# Sheet1.net
KiCad netlist of a schematic drawn in Altium Designer
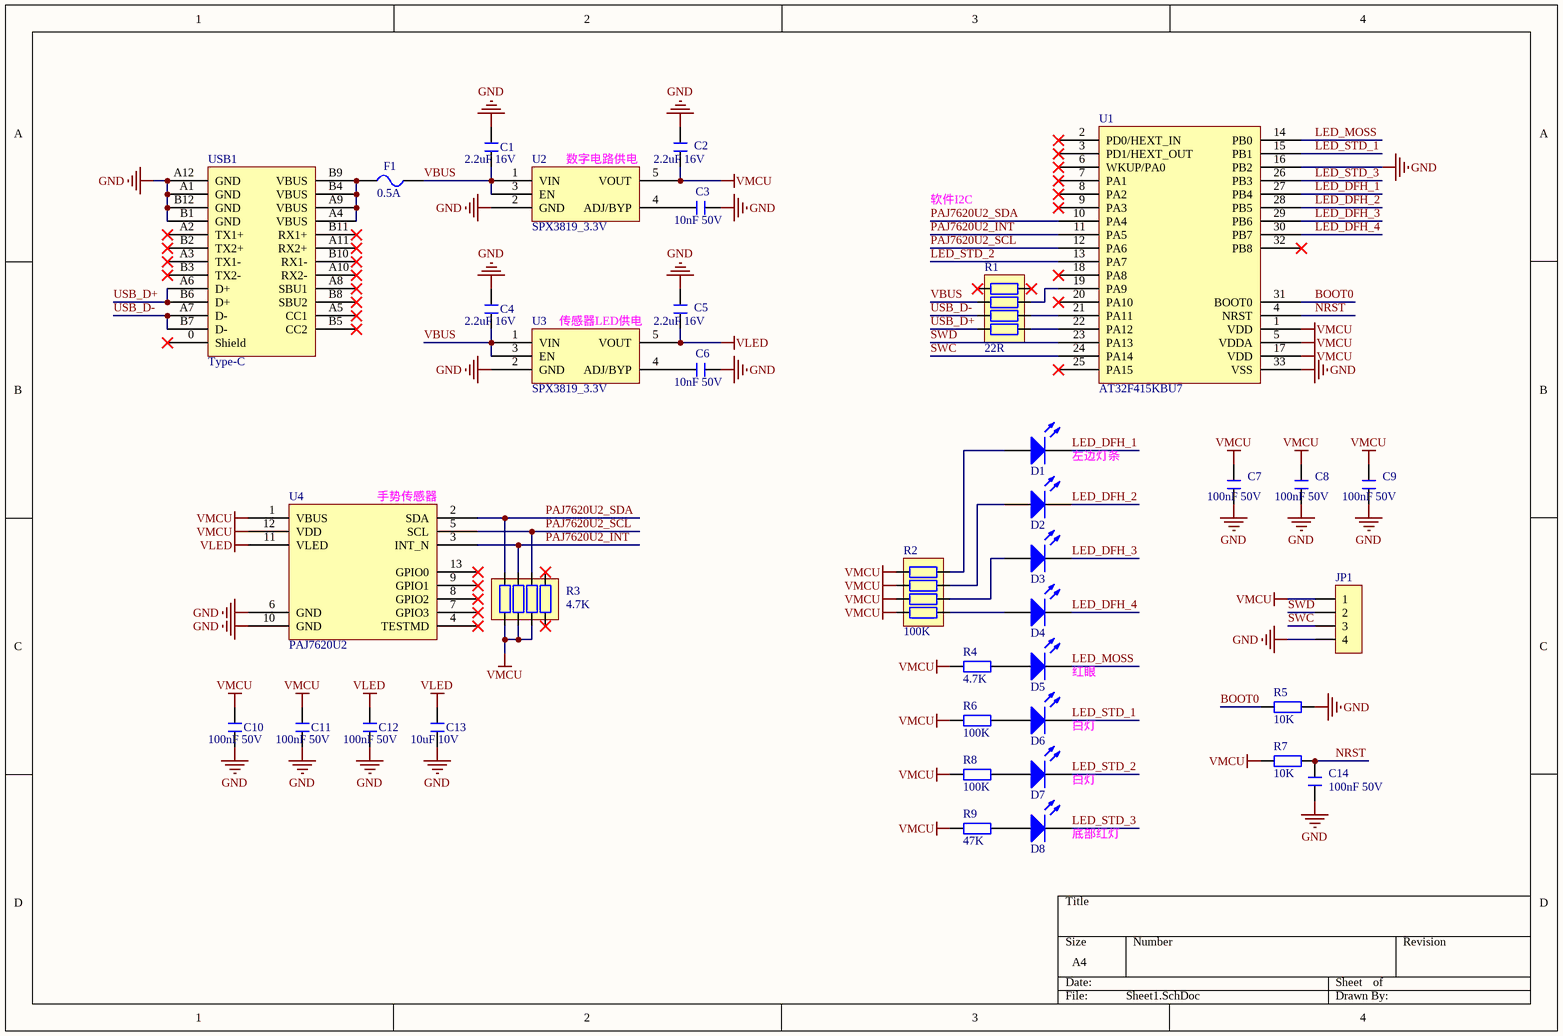
[diagram p0: Sheet1.SchDoc]

(export (version "E")
  (design (tool "Eeschema 10.0.6"))
  (components
    (comp (ref "C1")
      (value "2.2uF 16V")
      (footprint "C 0603_L")
      (description "贴片电容")
      (libsource (lib "0.1 - 电阻-电容-电感") (part "C"))
    )
    (comp (ref "C2")
      (value "2.2uF 16V")
      (footprint "C 0603_L")
      (description "贴片电容")
      (libsource (lib "0.1 - 电阻-电容-电感") (part "C"))
    )
    (comp (ref "C3")
      (value "10nF 50V")
      (footprint "C 0603_L")
      (description "贴片电容")
      (libsource (lib "0.1 - 电阻-电容-电感") (part "C"))
    )
    (comp (ref "C4")
      (value "2.2uF 16V")
      (footprint "C 0603_L")
      (description "贴片电容")
      (libsource (lib "0.1 - 电阻-电容-电感") (part "C"))
    )
    (comp (ref "C5")
      (value "2.2uF 16V")
      (footprint "C 0603_L")
      (description "贴片电容")
      (libsource (lib "0.1 - 电阻-电容-电感") (part "C"))
    )
    (comp (ref "C6")
      (value "10nF 50V")
      (footprint "C 0603_L")
      (description "贴片电容")
      (libsource (lib "0.1 - 电阻-电容-电感") (part "C"))
    )
    (comp (ref "C7")
      (value "100nF 50V")
      (footprint "C 0603_L")
      (description "贴片电容")
      (libsource (lib "0.1 - 电阻-电容-电感") (part "C"))
    )
    (comp (ref "C8")
      (value "100nF 50V")
      (footprint "C 0603_L")
      (description "贴片电容")
      (libsource (lib "0.1 - 电阻-电容-电感") (part "C"))
    )
    (comp (ref "C9")
      (value "100nF 50V")
      (footprint "C 0603_L")
      (description "贴片电容")
      (libsource (lib "0.1 - 电阻-电容-电感") (part "C"))
    )
    (comp (ref "C10")
      (value "100nF 50V")
      (footprint "C 0603_L")
      (description "贴片电容")
      (libsource (lib "0.1 - 电阻-电容-电感") (part "C"))
    )
    (comp (ref "C11")
      (value "100nF 50V")
      (footprint "C 0603_L")
      (description "贴片电容")
      (libsource (lib "0.1 - 电阻-电容-电感") (part "C"))
    )
    (comp (ref "C12")
      (value "100nF 50V")
      (footprint "C 0603_L")
      (description "贴片电容")
      (libsource (lib "0.1 - 电阻-电容-电感") (part "C"))
    )
    (comp (ref "C13")
      (value "10uF 10V")
      (footprint "C 0603_L")
      (description "贴片电容")
      (libsource (lib "0.1 - 电阻-电容-电感") (part "C"))
    )
    (comp (ref "C14")
      (value "100nF 50V")
      (footprint "C 0603_L")
      (description "贴片电容")
      (libsource (lib "0.1 - 电阻-电容-电感") (part "C"))
    )
    (comp (ref "D1")
      (value "LED")
      (footprint "R 0402_L")
      (description "发光二极管")
      (libsource (lib "0.3 - LED发光二极管") (part "LED"))
    )
    (comp (ref "D2")
      (value "LED")
      (footprint "R 0402_L")
      (description "发光二极管")
      (libsource (lib "0.3 - LED发光二极管") (part "LED"))
    )
    (comp (ref "D3")
      (value "LED")
      (footprint "R 0402_L")
      (description "发光二极管")
      (libsource (lib "0.3 - LED发光二极管") (part "LED"))
    )
    (comp (ref "D4")
      (value "LED")
      (footprint "R 0402_L")
      (description "发光二极管")
      (libsource (lib "0.3 - LED发光二极管") (part "LED"))
    )
    (comp (ref "D5")
      (value "LED")
      (footprint "LED_0603")
      (description "发光二极管")
      (libsource (lib "0.3 - LED发光二极管") (part "LED"))
    )
    (comp (ref "D6")
      (value "LED")
      (footprint "R 0402_L")
      (description "发光二极管")
      (libsource (lib "0.3 - LED发光二极管") (part "LED"))
    )
    (comp (ref "D7")
      (value "LED")
      (footprint "R 0402_L")
      (description "发光二极管")
      (libsource (lib "0.3 - LED发光二极管") (part "LED"))
    )
    (comp (ref "D8")
      (value "LED")
      (footprint "LED_0603")
      (description "发光二极管")
      (libsource (lib "0.3 - LED发光二极管") (part "LED"))
    )
    (comp (ref "F1")
      (value "0.5A")
      (footprint "FU 0805")
      (description "贴片保险丝")
      (fields (field (name "版权归属") "封装库来自淘宝卖家 ID：黄晶宝石"))
      (libsource (lib "0.5 - 保险丝-晶振-光耦") (part "FU"))
    )
    (comp (ref "JP1")
      (value "HDR-1X4")
      (footprint "HDR2.54-LI-4P")
      (description "4P接插件")
      (libsource (lib "5.1 - 接插件-脚距1.27") (part "Header 4"))
    )
    (comp (ref "R1")
      (value "22R")
      (footprint "RCA-8P4R-0603")
      (description "贴片排阻")
      (libsource (lib "0.1 - 电阻-电容-电感") (part "R-8P4R"))
    )
    (comp (ref "R2")
      (value "100K")
      (footprint "RCA-8P4R-0603")
      (description "贴片排阻")
      (libsource (lib "0.1 - 电阻-电容-电感") (part "R-8P4R"))
    )
    (comp (ref "R3")
      (value "4.7K")
      (footprint "RCA-8P4R-0603")
      (description "贴片排阻")
      (libsource (lib "") (part "R-8P4R_1"))
    )
    (comp (ref "R4")
      (value "4.7K")
      (footprint "R 0603_L")
      (description "贴片电阻")
      (libsource (lib "0.1 - 电阻-电容-电感") (part "R"))
    )
    (comp (ref "R5")
      (value "10K")
      (footprint "R 0603_L")
      (description "贴片电阻")
      (libsource (lib "0.1 - 电阻-电容-电感") (part "R"))
    )
    (comp (ref "R6")
      (value "100K")
      (footprint "R 0603_L")
      (description "贴片电阻")
      (libsource (lib "0.1 - 电阻-电容-电感") (part "R"))
    )
    (comp (ref "R7")
      (value "10K")
      (footprint "R 0603_L")
      (description "贴片电阻")
      (libsource (lib "0.1 - 电阻-电容-电感") (part "R"))
    )
    (comp (ref "R8")
      (value "100K")
      (footprint "R 0603_L")
      (description "贴片电阻")
      (libsource (lib "0.1 - 电阻-电容-电感") (part "R"))
    )
    (comp (ref "R9")
      (value "47K")
      (footprint "R 0603_L")
      (description "贴片电阻")
      (libsource (lib "0.1 - 电阻-电容-电感") (part "R"))
    )
    (comp (ref "U1")
      (value "AT32F415KBU7")
      (footprint "QFN-32 4X4")
      (description "基于ARM® 32位的Cortex®\r\n-M4微控制器，带64 K字节至256 K字节闪存、sLib、OTGFS、11个定时器、1个ADC、2个比较器、12个通信接口")
      (libsource (lib "mysch") (part "AT32F415K"))
    )
    (comp (ref "U2")
      (value "SPX3819_3.3V")
      (footprint "SOT23-5n")
      (description "16V 500mA LDO")
      (libsource (lib "mysch") (part "SPX3819"))
    )
    (comp (ref "U3")
      (value "SPX3819_3.3V")
      (footprint "SOT23-5n")
      (description "16V 500mA LDO")
      (libsource (lib "mysch") (part "SPX3819"))
    )
    (comp (ref "U4")
      (value "PAJ7620U2")
      (footprint "QFN-13_L5.2-W3.0_PAJ7620U2")
      (description "手势识别传感器")
      (libsource (lib "mysch") (part "PAJ7620U2"))
    )
    (comp (ref "USB1")
      (value "Type-C")
      (footprint "USB-TYPE-C_16PIN-MALE-TYPE-C-31-M-12")
      (libsource (lib "type-c") (part "Type-C"))
    )
  )
  (nets
    (net (code "1") (name "/BOOT0") (class "Default")
      (node (ref "R5") (pin "2") (pinfunction "2_2") (pintype "passive"))
      (node (ref "U1") (pin "31") (pinfunction "BOOT0_31") (pintype "passive"))
    )
    (net (code "2") (name "/LED_DFH_1") (class "Default")
      (node (ref "D1") (pin "2") (pinfunction "K_2") (pintype "passive"))
      (node (ref "U1") (pin "27") (pinfunction "PB4_27") (pintype "passive"))
    )
    (net (code "3") (name "/LED_DFH_2") (class "Default")
      (node (ref "D2") (pin "2") (pinfunction "K_2") (pintype "passive"))
      (node (ref "U1") (pin "28") (pinfunction "PB5_28") (pintype "passive"))
    )
    (net (code "4") (name "/LED_DFH_3") (class "Default")
      (node (ref "D3") (pin "2") (pinfunction "K_2") (pintype "passive"))
      (node (ref "U1") (pin "29") (pinfunction "PB6_29") (pintype "passive"))
    )
    (net (code "5") (name "/LED_DFH_4") (class "Default")
      (node (ref "D4") (pin "2") (pinfunction "K_2") (pintype "passive"))
      (node (ref "U1") (pin "30") (pinfunction "PB7_30") (pintype "passive"))
    )
    (net (code "6") (name "/LED_MOSS") (class "Default")
      (node (ref "D5") (pin "2") (pinfunction "K_2") (pintype "passive"))
      (node (ref "U1") (pin "14") (pinfunction "PB0_14") (pintype "passive"))
    )
    (net (code "7") (name "/LED_STD_1") (class "Default")
      (node (ref "D6") (pin "2") (pinfunction "K_2") (pintype "passive"))
      (node (ref "U1") (pin "15") (pinfunction "PB1_15") (pintype "passive"))
    )
    (net (code "8") (name "/LED_STD_2") (class "Default")
      (node (ref "D7") (pin "2") (pinfunction "K_2") (pintype "passive"))
      (node (ref "U1") (pin "13") (pinfunction "PA7_13") (pintype "passive"))
    )
    (net (code "9") (name "/LED_STD_3") (class "Default")
      (node (ref "D8") (pin "2") (pinfunction "K_2") (pintype "passive"))
      (node (ref "U1") (pin "26") (pinfunction "PB3_26") (pintype "passive"))
    )
    (net (code "10") (name "/NRST") (class "Default")
      (node (ref "C14") (pin "2") (pinfunction "2_2") (pintype "passive"))
      (node (ref "R7") (pin "1") (pinfunction "1_1") (pintype "passive"))
      (node (ref "U1") (pin "4") (pinfunction "NRST_4") (pintype "passive"))
    )
    (net (code "11") (name "/PAJ7620U2_INT") (class "Default")
      (node (ref "R3") (pin "7") (pinfunction "7_7") (pintype "passive"))
      (node (ref "U1") (pin "11") (pinfunction "PA5_11") (pintype "passive"))
      (node (ref "U4") (pin "3") (pinfunction "INT_N_3") (pintype "passive"))
    )
    (net (code "12") (name "/PAJ7620U2_SCL") (class "Default")
      (node (ref "R3") (pin "6") (pinfunction "6_6") (pintype "passive"))
      (node (ref "U1") (pin "12") (pinfunction "PA6_12") (pintype "passive"))
      (node (ref "U4") (pin "5") (pinfunction "SCL_5") (pintype "passive"))
    )
    (net (code "13") (name "/PAJ7620U2_SDA") (class "Default")
      (node (ref "R3") (pin "8") (pinfunction "8_8") (pintype "passive"))
      (node (ref "U1") (pin "10") (pinfunction "PA4_10") (pintype "passive"))
      (node (ref "U4") (pin "2") (pinfunction "SDA_2") (pintype "passive"))
    )
    (net (code "14") (name "/SWC") (class "Default")
      (node (ref "JP1") (pin "3") (pinfunction "3_3") (pintype "passive"))
      (node (ref "U1") (pin "24") (pinfunction "PA14_24") (pintype "passive"))
    )
    (net (code "15") (name "/SWD") (class "Default")
      (node (ref "JP1") (pin "2") (pinfunction "2_2") (pintype "passive"))
      (node (ref "U1") (pin "23") (pinfunction "PA13_23") (pintype "passive"))
    )
    (net (code "16") (name "/USB_D+") (class "Default")
      (node (ref "R1") (pin "4") (pinfunction "4_4") (pintype "passive"))
      (node (ref "USB1") (pin "A6") (pinfunction "D+_A6") (pintype "passive"))
      (node (ref "USB1") (pin "B6") (pinfunction "D+_B6") (pintype "passive"))
    )
    (net (code "17") (name "/USB_D-") (class "Default")
      (node (ref "R1") (pin "3") (pinfunction "3_3") (pintype "passive"))
      (node (ref "USB1") (pin "A7") (pinfunction "D-_A7") (pintype "passive"))
      (node (ref "USB1") (pin "B7") (pinfunction "D-_B7") (pintype "passive"))
    )
    (net (code "18") (name "/VBUS") (class "Default")
      (node (ref "C1") (pin "1") (pinfunction "1_1") (pintype "passive"))
      (node (ref "C4") (pin "1") (pinfunction "1_1") (pintype "passive"))
      (node (ref "F1") (pin "2") (pinfunction "2_2") (pintype "passive"))
      (node (ref "R1") (pin "2") (pinfunction "2_2") (pintype "passive"))
      (node (ref "U2") (pin "1") (pinfunction "VIN_1") (pintype "passive"))
      (node (ref "U2") (pin "3") (pinfunction "EN_3") (pintype "passive"))
      (node (ref "U3") (pin "1") (pinfunction "VIN_1") (pintype "passive"))
      (node (ref "U3") (pin "3") (pinfunction "EN_3") (pintype "passive"))
    )
    (net (code "19") (name "GND") (class "Default")
      (node (ref "C1") (pin "2") (pinfunction "2_2") (pintype "passive"))
      (node (ref "C10") (pin "2") (pinfunction "2_2") (pintype "passive"))
      (node (ref "C11") (pin "2") (pinfunction "2_2") (pintype "passive"))
      (node (ref "C12") (pin "2") (pinfunction "2_2") (pintype "passive"))
      (node (ref "C13") (pin "2") (pinfunction "2_2") (pintype "passive"))
      (node (ref "C14") (pin "1") (pinfunction "1_1") (pintype "passive"))
      (node (ref "C2") (pin "2") (pinfunction "2_2") (pintype "passive"))
      (node (ref "C3") (pin "1") (pinfunction "1_1") (pintype "passive"))
      (node (ref "C4") (pin "2") (pinfunction "2_2") (pintype "passive"))
      (node (ref "C5") (pin "2") (pinfunction "2_2") (pintype "passive"))
      (node (ref "C6") (pin "1") (pinfunction "1_1") (pintype "passive"))
      (node (ref "C7") (pin "1") (pinfunction "1_1") (pintype "passive"))
      (node (ref "C8") (pin "1") (pinfunction "1_1") (pintype "passive"))
      (node (ref "C9") (pin "1") (pinfunction "1_1") (pintype "passive"))
      (node (ref "JP1") (pin "4") (pinfunction "4_4") (pintype "passive"))
      (node (ref "R5") (pin "1") (pinfunction "1_1") (pintype "passive"))
      (node (ref "U1") (pin "16") (pinfunction "PB2_16") (pintype "passive"))
      (node (ref "U1") (pin "33") (pinfunction "VSS_33") (pintype "passive"))
      (node (ref "U2") (pin "2") (pinfunction "GND_2") (pintype "passive"))
      (node (ref "U3") (pin "2") (pinfunction "GND_2") (pintype "passive"))
      (node (ref "U4") (pin "10") (pinfunction "GND_10") (pintype "passive"))
      (node (ref "U4") (pin "6") (pinfunction "GND_6") (pintype "passive"))
      (node (ref "USB1") (pin "A1") (pinfunction "GND_A1") (pintype "passive"))
      (node (ref "USB1") (pin "A12") (pinfunction "GND_A12") (pintype "passive"))
      (node (ref "USB1") (pin "B1") (pinfunction "GND_B1") (pintype "passive"))
      (node (ref "USB1") (pin "B12") (pinfunction "GND_B12") (pintype "passive"))
    )
    (net (code "20") (name "Net-(D1-A)") (class "Default")
      (node (ref "D1") (pin "1") (pinfunction "A_1") (pintype "passive"))
      (node (ref "R2") (pin "8") (pinfunction "8_8") (pintype "passive"))
    )
    (net (code "21") (name "Net-(D2-A)") (class "Default")
      (node (ref "D2") (pin "1") (pinfunction "A_1") (pintype "passive"))
      (node (ref "R2") (pin "7") (pinfunction "7_7") (pintype "passive"))
    )
    (net (code "22") (name "Net-(D3-A)") (class "Default")
      (node (ref "D3") (pin "1") (pinfunction "A_1") (pintype "passive"))
      (node (ref "R2") (pin "6") (pinfunction "6_6") (pintype "passive"))
    )
    (net (code "23") (name "Net-(D4-A)") (class "Default")
      (node (ref "D4") (pin "1") (pinfunction "A_1") (pintype "passive"))
      (node (ref "R2") (pin "5") (pinfunction "5_5") (pintype "passive"))
    )
    (net (code "24") (name "Net-(D5-A)") (class "Default")
      (node (ref "D5") (pin "1") (pinfunction "A_1") (pintype "passive"))
      (node (ref "R4") (pin "1") (pinfunction "1_1") (pintype "passive"))
    )
    (net (code "25") (name "Net-(D6-A)") (class "Default")
      (node (ref "D6") (pin "1") (pinfunction "A_1") (pintype "passive"))
      (node (ref "R6") (pin "1") (pinfunction "1_1") (pintype "passive"))
    )
    (net (code "26") (name "Net-(D7-A)") (class "Default")
      (node (ref "D7") (pin "1") (pinfunction "A_1") (pintype "passive"))
      (node (ref "R8") (pin "1") (pinfunction "1_1") (pintype "passive"))
    )
    (net (code "27") (name "Net-(D8-A)") (class "Default")
      (node (ref "D8") (pin "1") (pinfunction "A_1") (pintype "passive"))
      (node (ref "R9") (pin "1") (pinfunction "1_1") (pintype "passive"))
    )
    (net (code "28") (name "Net-(F1-Pad1)") (class "Default")
      (node (ref "F1") (pin "1") (pinfunction "1_1") (pintype "passive"))
      (node (ref "USB1") (pin "A4") (pinfunction "VBUS_A4") (pintype "passive"))
      (node (ref "USB1") (pin "A9") (pinfunction "VBUS_A9") (pintype "passive"))
      (node (ref "USB1") (pin "B4") (pinfunction "VBUS_B4") (pintype "passive"))
      (node (ref "USB1") (pin "B9") (pinfunction "VBUS_B9") (pintype "passive"))
    )
    (net (code "29") (name "Net-(U1-PA9)") (class "Default")
      (node (ref "R1") (pin "7") (pinfunction "7_7") (pintype "passive"))
      (node (ref "U1") (pin "19") (pinfunction "PA9_19") (pintype "passive"))
    )
    (net (code "30") (name "Net-(U1-PA11)") (class "Default")
      (node (ref "R1") (pin "6") (pinfunction "6_6") (pintype "passive"))
      (node (ref "U1") (pin "21") (pinfunction "PA11_21") (pintype "passive"))
    )
    (net (code "31") (name "Net-(U1-PA12)") (class "Default")
      (node (ref "R1") (pin "5") (pinfunction "5_5") (pintype "passive"))
      (node (ref "U1") (pin "22") (pinfunction "PA12_22") (pintype "passive"))
    )
    (net (code "32") (name "Net-(U2-ADJ{slash}BYP)") (class "Default")
      (node (ref "C3") (pin "2") (pinfunction "2_2") (pintype "passive"))
      (node (ref "U2") (pin "4") (pinfunction "ADJ/BYP_4") (pintype "passive"))
    )
    (net (code "33") (name "Net-(U3-ADJ{slash}BYP)") (class "Default")
      (node (ref "C6") (pin "2") (pinfunction "2_2") (pintype "passive"))
      (node (ref "U3") (pin "4") (pinfunction "ADJ/BYP_4") (pintype "passive"))
    )
    (net (code "34") (name "VLED") (class "Default")
      (node (ref "C12") (pin "1") (pinfunction "1_1") (pintype "passive"))
      (node (ref "C13") (pin "1") (pinfunction "1_1") (pintype "passive"))
      (node (ref "C5") (pin "1") (pinfunction "1_1") (pintype "passive"))
      (node (ref "U3") (pin "5") (pinfunction "VOUT_5") (pintype "passive"))
      (node (ref "U4") (pin "11") (pinfunction "VLED_11") (pintype "passive"))
    )
    (net (code "35") (name "VMCU") (class "Default")
      (node (ref "C10") (pin "1") (pinfunction "1_1") (pintype "passive"))
      (node (ref "C11") (pin "1") (pinfunction "1_1") (pintype "passive"))
      (node (ref "C2") (pin "1") (pinfunction "1_1") (pintype "passive"))
      (node (ref "C7") (pin "2") (pinfunction "2_2") (pintype "passive"))
      (node (ref "C8") (pin "2") (pinfunction "2_2") (pintype "passive"))
      (node (ref "C9") (pin "2") (pinfunction "2_2") (pintype "passive"))
      (node (ref "JP1") (pin "1") (pinfunction "1_1") (pintype "passive"))
      (node (ref "R2") (pin "1") (pinfunction "1_1") (pintype "passive"))
      (node (ref "R2") (pin "2") (pinfunction "2_2") (pintype "passive"))
      (node (ref "R2") (pin "3") (pinfunction "3_3") (pintype "passive"))
      (node (ref "R2") (pin "4") (pinfunction "4_4") (pintype "passive"))
      (node (ref "R3") (pin "1") (pinfunction "1_1") (pintype "passive"))
      (node (ref "R3") (pin "2") (pinfunction "2_2") (pintype "passive"))
      (node (ref "R3") (pin "3") (pinfunction "3_3") (pintype "passive"))
      (node (ref "R4") (pin "2") (pinfunction "2_2") (pintype "passive"))
      (node (ref "R6") (pin "2") (pinfunction "2_2") (pintype "passive"))
      (node (ref "R7") (pin "2") (pinfunction "2_2") (pintype "passive"))
      (node (ref "R8") (pin "2") (pinfunction "2_2") (pintype "passive"))
      (node (ref "R9") (pin "2") (pinfunction "2_2") (pintype "passive"))
      (node (ref "U1") (pin "1") (pinfunction "VDD_1") (pintype "passive"))
      (node (ref "U1") (pin "17") (pinfunction "VDD_17") (pintype "passive"))
      (node (ref "U1") (pin "5") (pinfunction "VDDA_5") (pintype "passive"))
      (node (ref "U2") (pin "5") (pinfunction "VOUT_5") (pintype "passive"))
      (node (ref "U4") (pin "1") (pinfunction "VBUS_1") (pintype "passive"))
      (node (ref "U4") (pin "12") (pinfunction "VDD_12") (pintype "passive"))
    )
    (net (code "36") (name "unconnected-(R1-Pad1)") (class "Default")
      (node (ref "R1") (pin "1") (pinfunction "1_1") (pintype "passive+no_connect"))
    )
    (net (code "37") (name "unconnected-(R1-Pad8)") (class "Default")
      (node (ref "R1") (pin "8") (pinfunction "8_8") (pintype "passive+no_connect"))
    )
    (net (code "38") (name "unconnected-(R3-Pad4)") (class "Default")
      (node (ref "R3") (pin "4") (pinfunction "4_4") (pintype "passive+no_connect"))
    )
    (net (code "39") (name "unconnected-(R3-Pad5)") (class "Default")
      (node (ref "R3") (pin "5") (pinfunction "5_5") (pintype "passive+no_connect"))
    )
    (net (code "40") (name "unconnected-(U1-PA1-Pad7)") (class "Default")
      (node (ref "U1") (pin "7") (pinfunction "PA1_7") (pintype "passive+no_connect"))
    )
    (net (code "41") (name "unconnected-(U1-PA2-Pad8)") (class "Default")
      (node (ref "U1") (pin "8") (pinfunction "PA2_8") (pintype "passive+no_connect"))
    )
    (net (code "42") (name "unconnected-(U1-PA3-Pad9)") (class "Default")
      (node (ref "U1") (pin "9") (pinfunction "PA3_9") (pintype "passive+no_connect"))
    )
    (net (code "43") (name "unconnected-(U1-PA8-Pad18)") (class "Default")
      (node (ref "U1") (pin "18") (pinfunction "PA8_18") (pintype "passive+no_connect"))
    )
    (net (code "44") (name "unconnected-(U1-PA10-Pad20)") (class "Default")
      (node (ref "U1") (pin "20") (pinfunction "PA10_20") (pintype "passive+no_connect"))
    )
    (net (code "45") (name "unconnected-(U1-PA15-Pad25)") (class "Default")
      (node (ref "U1") (pin "25") (pinfunction "PA15_25") (pintype "passive+no_connect"))
    )
    (net (code "46") (name "unconnected-(U1-PB8-Pad32)") (class "Default")
      (node (ref "U1") (pin "32") (pinfunction "PB8_32") (pintype "passive+no_connect"))
    )
    (net (code "47") (name "unconnected-(U1-PD0{slash}HEXT_IN-Pad2)") (class "Default")
      (node (ref "U1") (pin "2") (pinfunction "PD0/HEXT_IN_2") (pintype "passive+no_connect"))
    )
    (net (code "48") (name "unconnected-(U1-PD1{slash}HEXT_OUT-Pad3)") (class "Default")
      (node (ref "U1") (pin "3") (pinfunction "PD1/HEXT_OUT_3") (pintype "passive+no_connect"))
    )
    (net (code "49") (name "unconnected-(U1-WKUP{slash}PA0-Pad6)") (class "Default")
      (node (ref "U1") (pin "6") (pinfunction "WKUP/PA0_6") (pintype "passive+no_connect"))
    )
    (net (code "50") (name "unconnected-(U4-GPIO0-Pad13)") (class "Default")
      (node (ref "U4") (pin "13") (pinfunction "GPIO0_13") (pintype "passive+no_connect"))
    )
    (net (code "51") (name "unconnected-(U4-GPIO1-Pad9)") (class "Default")
      (node (ref "U4") (pin "9") (pinfunction "GPIO1_9") (pintype "passive+no_connect"))
    )
    (net (code "52") (name "unconnected-(U4-GPIO2-Pad8)") (class "Default")
      (node (ref "U4") (pin "8") (pinfunction "GPIO2_8") (pintype "passive+no_connect"))
    )
    (net (code "53") (name "unconnected-(U4-GPIO3-Pad7)") (class "Default")
      (node (ref "U4") (pin "7") (pinfunction "GPIO3_7") (pintype "passive+no_connect"))
    )
    (net (code "54") (name "unconnected-(U4-TESTMD-Pad4)") (class "Default")
      (node (ref "U4") (pin "4") (pinfunction "TESTMD_4") (pintype "passive+no_connect"))
    )
    (net (code "55") (name "unconnected-(USB1-CC1-PadA5)") (class "Default")
      (node (ref "USB1") (pin "A5") (pinfunction "CC1_A5") (pintype "passive+no_connect"))
    )
    (net (code "56") (name "unconnected-(USB1-CC2-PadB5)") (class "Default")
      (node (ref "USB1") (pin "B5") (pinfunction "CC2_B5") (pintype "passive+no_connect"))
    )
    (net (code "57") (name "unconnected-(USB1-RX1+-PadB11)") (class "Default")
      (node (ref "USB1") (pin "B11") (pinfunction "RX1+_B11") (pintype "passive+no_connect"))
    )
    (net (code "58") (name "unconnected-(USB1-RX1--PadB10)") (class "Default")
      (node (ref "USB1") (pin "B10") (pinfunction "RX1-_B10") (pintype "passive+no_connect"))
    )
    (net (code "59") (name "unconnected-(USB1-RX2+-PadA11)") (class "Default")
      (node (ref "USB1") (pin "A11") (pinfunction "RX2+_A11") (pintype "passive+no_connect"))
    )
    (net (code "60") (name "unconnected-(USB1-RX2--PadA10)") (class "Default")
      (node (ref "USB1") (pin "A10") (pinfunction "RX2-_A10") (pintype "passive+no_connect"))
    )
    (net (code "61") (name "unconnected-(USB1-SBU1-PadA8)") (class "Default")
      (node (ref "USB1") (pin "A8") (pinfunction "SBU1_A8") (pintype "passive+no_connect"))
    )
    (net (code "62") (name "unconnected-(USB1-SBU2-PadB8)") (class "Default")
      (node (ref "USB1") (pin "B8") (pinfunction "SBU2_B8") (pintype "passive+no_connect"))
    )
    (net (code "63") (name "unconnected-(USB1-Shield-Pad0)") (class "Default")
      (node (ref "USB1") (pin "0") (pinfunction "Shield_0") (pintype "passive+no_connect"))
    )
    (net (code "64") (name "unconnected-(USB1-TX1+-PadA2)") (class "Default")
      (node (ref "USB1") (pin "A2") (pinfunction "TX1+_A2") (pintype "passive+no_connect"))
    )
    (net (code "65") (name "unconnected-(USB1-TX1--PadA3)") (class "Default")
      (node (ref "USB1") (pin "A3") (pinfunction "TX1-_A3") (pintype "passive+no_connect"))
    )
    (net (code "66") (name "unconnected-(USB1-TX2+-PadB2)") (class "Default")
      (node (ref "USB1") (pin "B2") (pinfunction "TX2+_B2") (pintype "passive+no_connect"))
    )
    (net (code "67") (name "unconnected-(USB1-TX2--PadB3)") (class "Default")
      (node (ref "USB1") (pin "B3") (pinfunction "TX2-_B3") (pintype "passive+no_connect"))
    )
  )
)
